# CTL_RELAY_SHEET2_CCU_HAS.net
KiCad netlist of a schematic drawn in Altium Designer
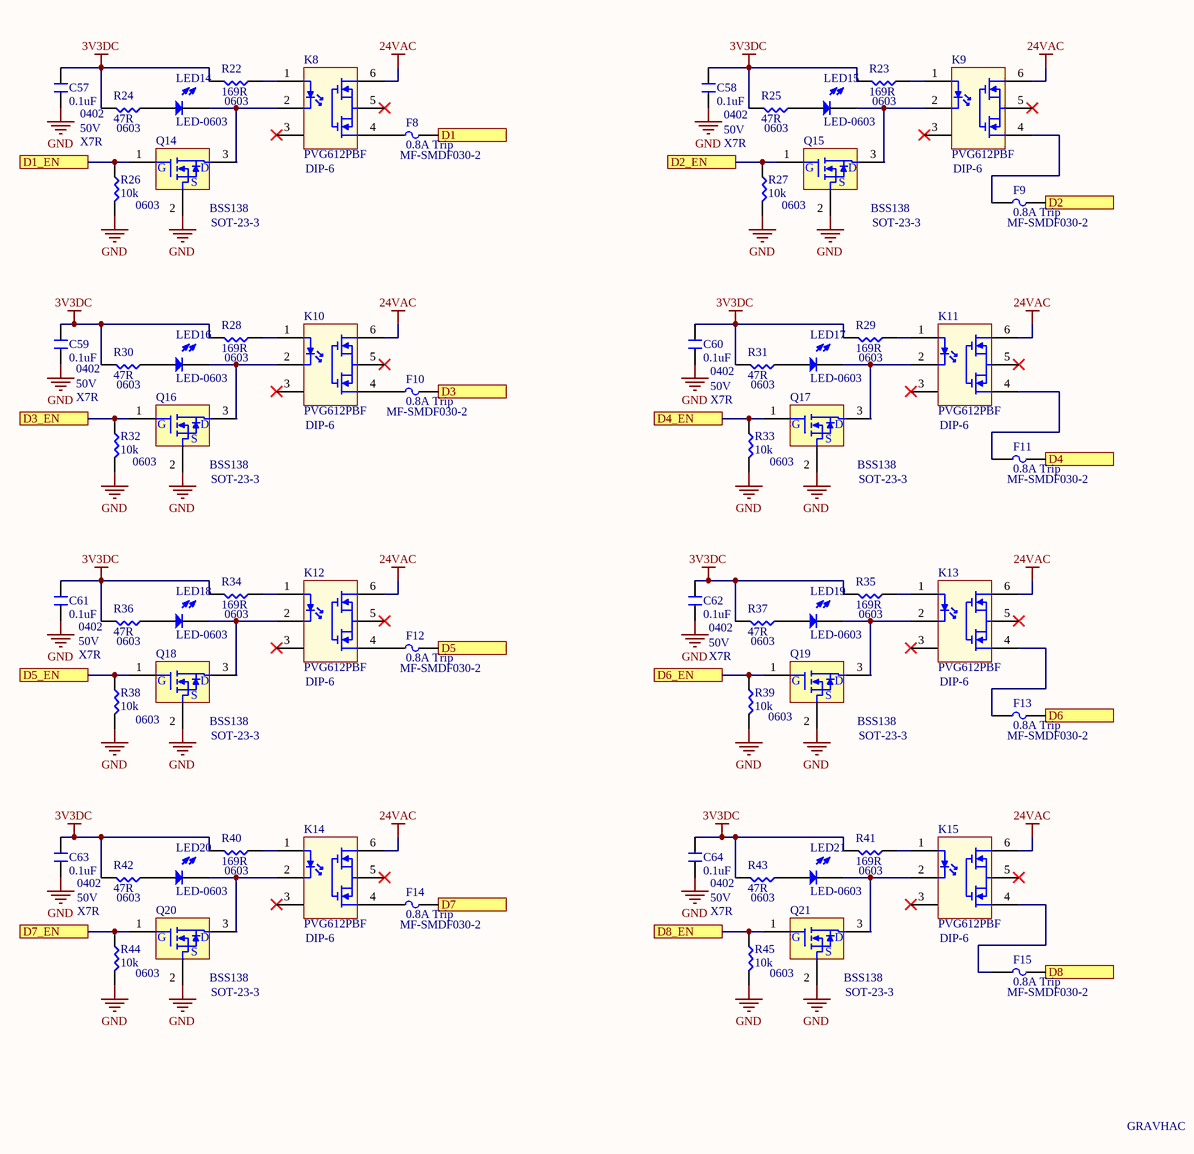
[diagram p0: CTL_RELAY_SHEET2_CCU_HAS.SchDoc]

(export (version "E")
  (design (tool "Eeschema 10.0.6"))
  (components
    (comp (ref "C57")
      (value "0.1uF")
      (footprint "NonPolar-0402")
      (libsource (lib "GravLib") (part "Cap - 0402"))
    )
    (comp (ref "C58")
      (value "0.1uF")
      (footprint "NonPolar-0402")
      (libsource (lib "GravLib") (part "Cap - 0402"))
    )
    (comp (ref "C59")
      (value "0.1uF")
      (footprint "NonPolar-0402")
      (libsource (lib "GravLib") (part "Cap - 0402"))
    )
    (comp (ref "C60")
      (value "0.1uF")
      (footprint "NonPolar-0402")
      (libsource (lib "GravLib") (part "Cap - 0402"))
    )
    (comp (ref "C61")
      (value "0.1uF")
      (footprint "NonPolar-0402")
      (libsource (lib "GravLib") (part "Cap - 0402"))
    )
    (comp (ref "C62")
      (value "0.1uF")
      (footprint "NonPolar-0402")
      (libsource (lib "GravLib") (part "Cap - 0402"))
    )
    (comp (ref "C63")
      (value "0.1uF")
      (footprint "NonPolar-0402")
      (libsource (lib "GravLib") (part "Cap - 0402"))
    )
    (comp (ref "C64")
      (value "0.1uF")
      (footprint "NonPolar-0402")
      (libsource (lib "GravLib") (part "Cap - 0402"))
    )
    (comp (ref "F8")
      (value "0.8A Trip")
      (footprint "Fuse-MF-SMDF030-2")
      (libsource (lib "GravLib") (part "Fuse-MF-SMDF030-2"))
    )
    (comp (ref "F9")
      (value "0.8A Trip")
      (footprint "Fuse-MF-SMDF030-2")
      (libsource (lib "GravLib") (part "Fuse-MF-SMDF030-2"))
    )
    (comp (ref "F10")
      (value "0.8A Trip")
      (footprint "Fuse-MF-SMDF030-2")
      (libsource (lib "GravLib") (part "Fuse-MF-SMDF030-2"))
    )
    (comp (ref "F11")
      (value "0.8A Trip")
      (footprint "Fuse-MF-SMDF030-2")
      (libsource (lib "GravLib") (part "Fuse-MF-SMDF030-2"))
    )
    (comp (ref "F12")
      (value "0.8A Trip")
      (footprint "Fuse-MF-SMDF030-2")
      (libsource (lib "GravLib") (part "Fuse-MF-SMDF030-2"))
    )
    (comp (ref "F13")
      (value "0.8A Trip")
      (footprint "Fuse-MF-SMDF030-2")
      (libsource (lib "GravLib") (part "Fuse-MF-SMDF030-2"))
    )
    (comp (ref "F14")
      (value "0.8A Trip")
      (footprint "Fuse-MF-SMDF030-2")
      (libsource (lib "GravLib") (part "Fuse-MF-SMDF030-2"))
    )
    (comp (ref "F15")
      (value "0.8A Trip")
      (footprint "Fuse-MF-SMDF030-2")
      (libsource (lib "GravLib") (part "Fuse-MF-SMDF030-2"))
    )
    (comp (ref "K8")
      (value "PVG612PBF")
      (footprint "PVG612PBF")
      (description "PhotoVoltaic Relay")
      (libsource (lib "GravLib") (part "PVG612PBF"))
    )
    (comp (ref "K9")
      (value "PVG612PBF")
      (footprint "PVG612PBF")
      (description "PhotoVoltaic Relay")
      (libsource (lib "GravLib") (part "PVG612PBF"))
    )
    (comp (ref "K10")
      (value "PVG612PBF")
      (footprint "PVG612PBF")
      (description "PhotoVoltaic Relay")
      (libsource (lib "GravLib") (part "PVG612PBF"))
    )
    (comp (ref "K11")
      (value "PVG612PBF")
      (footprint "PVG612PBF")
      (description "PhotoVoltaic Relay")
      (libsource (lib "GravLib") (part "PVG612PBF"))
    )
    (comp (ref "K12")
      (value "PVG612PBF")
      (footprint "PVG612PBF")
      (description "PhotoVoltaic Relay")
      (libsource (lib "GravLib") (part "PVG612PBF"))
    )
    (comp (ref "K13")
      (value "PVG612PBF")
      (footprint "PVG612PBF")
      (description "PhotoVoltaic Relay")
      (libsource (lib "GravLib") (part "PVG612PBF"))
    )
    (comp (ref "K14")
      (value "PVG612PBF")
      (footprint "PVG612PBF")
      (description "PhotoVoltaic Relay")
      (libsource (lib "GravLib") (part "PVG612PBF"))
    )
    (comp (ref "K15")
      (value "PVG612PBF")
      (footprint "PVG612PBF")
      (description "PhotoVoltaic Relay")
      (libsource (lib "GravLib") (part "PVG612PBF"))
    )
    (comp (ref "LED14")
      (value "LED-0603")
      (footprint "LED-0603")
      (libsource (lib "GravLib") (part "LED-0603"))
    )
    (comp (ref "LED15")
      (value "LED-0603")
      (footprint "LED-0603")
      (libsource (lib "GravLib") (part "LED-0603"))
    )
    (comp (ref "LED16")
      (value "LED-0603")
      (footprint "LED-0603")
      (libsource (lib "GravLib") (part "LED-0603"))
    )
    (comp (ref "LED17")
      (value "LED-0603")
      (footprint "LED-0603")
      (libsource (lib "GravLib") (part "LED-0603"))
    )
    (comp (ref "LED18")
      (value "LED-0603")
      (footprint "LED-0603")
      (libsource (lib "GravLib") (part "LED-0603"))
    )
    (comp (ref "LED19")
      (value "LED-0603")
      (footprint "LED-0603")
      (libsource (lib "GravLib") (part "LED-0603"))
    )
    (comp (ref "LED20")
      (value "LED-0603")
      (footprint "LED-0603")
      (libsource (lib "GravLib") (part "LED-0603"))
    )
    (comp (ref "LED21")
      (value "LED-0603")
      (footprint "LED-0603")
      (libsource (lib "GravLib") (part "LED-0603"))
    )
    (comp (ref "Q14") (value "BSS138") (footprint "BSS138-SOT23") (libsource (lib "GravLib") (part "BSS138")))
    (comp (ref "Q15") (value "BSS138") (footprint "BSS138-SOT23") (libsource (lib "GravLib") (part "BSS138")))
    (comp (ref "Q16") (value "BSS138") (footprint "BSS138-SOT23") (libsource (lib "GravLib") (part "BSS138")))
    (comp (ref "Q17") (value "BSS138") (footprint "BSS138-SOT23") (libsource (lib "GravLib") (part "BSS138")))
    (comp (ref "Q18") (value "BSS138") (footprint "BSS138-SOT23") (libsource (lib "GravLib") (part "BSS138")))
    (comp (ref "Q19") (value "BSS138") (footprint "BSS138-SOT23") (libsource (lib "GravLib") (part "BSS138")))
    (comp (ref "Q20") (value "BSS138") (footprint "BSS138-SOT23") (libsource (lib "GravLib") (part "BSS138")))
    (comp (ref "Q21") (value "BSS138") (footprint "BSS138-SOT23") (libsource (lib "GravLib") (part "BSS138")))
    (comp (ref "R22")
      (value "169R")
      (footprint "NonPolar-0603")
      (libsource (lib "GravLib") (part "Res - 0603"))
    )
    (comp (ref "R23")
      (value "169R")
      (footprint "NonPolar-0603")
      (libsource (lib "GravLib") (part "Res - 0603"))
    )
    (comp (ref "R24")
      (value "47R")
      (footprint "NonPolar-0603")
      (libsource (lib "GravLib") (part "Res - 0603"))
    )
    (comp (ref "R25")
      (value "47R")
      (footprint "NonPolar-0603")
      (libsource (lib "GravLib") (part "Res - 0603"))
    )
    (comp (ref "R26")
      (value "10k")
      (footprint "NonPolar-0603")
      (libsource (lib "GravLib") (part "Res - 0603"))
    )
    (comp (ref "R27")
      (value "10k")
      (footprint "NonPolar-0603")
      (libsource (lib "GravLib") (part "Res - 0603"))
    )
    (comp (ref "R28")
      (value "169R")
      (footprint "NonPolar-0603")
      (libsource (lib "GravLib") (part "Res - 0603"))
    )
    (comp (ref "R29")
      (value "169R")
      (footprint "NonPolar-0603")
      (libsource (lib "GravLib") (part "Res - 0603"))
    )
    (comp (ref "R30")
      (value "47R")
      (footprint "NonPolar-0603")
      (libsource (lib "GravLib") (part "Res - 0603"))
    )
    (comp (ref "R31")
      (value "47R")
      (footprint "NonPolar-0603")
      (libsource (lib "GravLib") (part "Res - 0603"))
    )
    (comp (ref "R32")
      (value "10k")
      (footprint "NonPolar-0603")
      (libsource (lib "GravLib") (part "Res - 0603"))
    )
    (comp (ref "R33")
      (value "10k")
      (footprint "NonPolar-0603")
      (libsource (lib "GravLib") (part "Res - 0603"))
    )
    (comp (ref "R34")
      (value "169R")
      (footprint "NonPolar-0603")
      (libsource (lib "GravLib") (part "Res - 0603"))
    )
    (comp (ref "R35")
      (value "169R")
      (footprint "NonPolar-0603")
      (libsource (lib "GravLib") (part "Res - 0603"))
    )
    (comp (ref "R36")
      (value "47R")
      (footprint "NonPolar-0603")
      (libsource (lib "GravLib") (part "Res - 0603"))
    )
    (comp (ref "R37")
      (value "47R")
      (footprint "NonPolar-0603")
      (libsource (lib "GravLib") (part "Res - 0603"))
    )
    (comp (ref "R38")
      (value "10k")
      (footprint "NonPolar-0603")
      (libsource (lib "GravLib") (part "Res - 0603"))
    )
    (comp (ref "R39")
      (value "10k")
      (footprint "NonPolar-0603")
      (libsource (lib "GravLib") (part "Res - 0603"))
    )
    (comp (ref "R40")
      (value "169R")
      (footprint "NonPolar-0603")
      (libsource (lib "GravLib") (part "Res - 0603"))
    )
    (comp (ref "R41")
      (value "169R")
      (footprint "NonPolar-0603")
      (libsource (lib "GravLib") (part "Res - 0603"))
    )
    (comp (ref "R42")
      (value "47R")
      (footprint "NonPolar-0603")
      (libsource (lib "GravLib") (part "Res - 0603"))
    )
    (comp (ref "R43")
      (value "47R")
      (footprint "NonPolar-0603")
      (libsource (lib "GravLib") (part "Res - 0603"))
    )
    (comp (ref "R44")
      (value "10k")
      (footprint "NonPolar-0603")
      (libsource (lib "GravLib") (part "Res - 0603"))
    )
    (comp (ref "R45")
      (value "10k")
      (footprint "NonPolar-0603")
      (libsource (lib "GravLib") (part "Res - 0603"))
    )
  )
  (nets
    (net (code "1") (name "/D1") (class "Default")
      (node (ref "F8") (pin "2") (pinfunction "2_2") (pintype "passive"))
    )
    (net (code "2") (name "/D1_EN") (class "Default")
      (node (ref "Q14") (pin "1") (pinfunction "G_1") (pintype "passive"))
      (node (ref "R26") (pin "2") (pinfunction "2_2") (pintype "passive"))
    )
    (net (code "3") (name "/D2") (class "Default")
      (node (ref "F9") (pin "2") (pinfunction "2_2") (pintype "passive"))
    )
    (net (code "4") (name "/D2_EN") (class "Default")
      (node (ref "Q15") (pin "1") (pinfunction "G_1") (pintype "passive"))
      (node (ref "R27") (pin "2") (pinfunction "2_2") (pintype "passive"))
    )
    (net (code "5") (name "/D3") (class "Default")
      (node (ref "F10") (pin "2") (pinfunction "2_2") (pintype "passive"))
    )
    (net (code "6") (name "/D3_EN") (class "Default")
      (node (ref "Q16") (pin "1") (pinfunction "G_1") (pintype "passive"))
      (node (ref "R32") (pin "2") (pinfunction "2_2") (pintype "passive"))
    )
    (net (code "7") (name "/D4") (class "Default")
      (node (ref "F11") (pin "2") (pinfunction "2_2") (pintype "passive"))
    )
    (net (code "8") (name "/D4_EN") (class "Default")
      (node (ref "Q17") (pin "1") (pinfunction "G_1") (pintype "passive"))
      (node (ref "R33") (pin "2") (pinfunction "2_2") (pintype "passive"))
    )
    (net (code "9") (name "/D5") (class "Default")
      (node (ref "F12") (pin "2") (pinfunction "2_2") (pintype "passive"))
    )
    (net (code "10") (name "/D5_EN") (class "Default")
      (node (ref "Q18") (pin "1") (pinfunction "G_1") (pintype "passive"))
      (node (ref "R38") (pin "2") (pinfunction "2_2") (pintype "passive"))
    )
    (net (code "11") (name "/D6") (class "Default")
      (node (ref "F13") (pin "2") (pinfunction "2_2") (pintype "passive"))
    )
    (net (code "12") (name "/D6_EN") (class "Default")
      (node (ref "Q19") (pin "1") (pinfunction "G_1") (pintype "passive"))
      (node (ref "R39") (pin "2") (pinfunction "2_2") (pintype "passive"))
    )
    (net (code "13") (name "/D7") (class "Default")
      (node (ref "F14") (pin "2") (pinfunction "2_2") (pintype "passive"))
    )
    (net (code "14") (name "/D7_EN") (class "Default")
      (node (ref "Q20") (pin "1") (pinfunction "G_1") (pintype "passive"))
      (node (ref "R44") (pin "2") (pinfunction "2_2") (pintype "passive"))
    )
    (net (code "15") (name "/D8") (class "Default")
      (node (ref "F15") (pin "2") (pinfunction "2_2") (pintype "passive"))
    )
    (net (code "16") (name "/D8_EN") (class "Default")
      (node (ref "Q21") (pin "1") (pinfunction "G_1") (pintype "passive"))
      (node (ref "R45") (pin "2") (pinfunction "2_2") (pintype "passive"))
    )
    (net (code "17") (name "3V3DC") (class "Default")
      (node (ref "C57") (pin "2") (pinfunction "2_2") (pintype "passive"))
      (node (ref "C58") (pin "2") (pinfunction "2_2") (pintype "passive"))
      (node (ref "C59") (pin "2") (pinfunction "2_2") (pintype "passive"))
      (node (ref "C60") (pin "2") (pinfunction "2_2") (pintype "passive"))
      (node (ref "C61") (pin "2") (pinfunction "2_2") (pintype "passive"))
      (node (ref "C62") (pin "2") (pinfunction "2_2") (pintype "passive"))
      (node (ref "C63") (pin "2") (pinfunction "2_2") (pintype "passive"))
      (node (ref "C64") (pin "2") (pinfunction "2_2") (pintype "passive"))
      (node (ref "R22") (pin "1") (pinfunction "1_1") (pintype "passive"))
      (node (ref "R23") (pin "1") (pinfunction "1_1") (pintype "passive"))
      (node (ref "R24") (pin "1") (pinfunction "1_1") (pintype "passive"))
      (node (ref "R25") (pin "1") (pinfunction "1_1") (pintype "passive"))
      (node (ref "R28") (pin "1") (pinfunction "1_1") (pintype "passive"))
      (node (ref "R29") (pin "1") (pinfunction "1_1") (pintype "passive"))
      (node (ref "R30") (pin "1") (pinfunction "1_1") (pintype "passive"))
      (node (ref "R31") (pin "1") (pinfunction "1_1") (pintype "passive"))
      (node (ref "R34") (pin "1") (pinfunction "1_1") (pintype "passive"))
      (node (ref "R35") (pin "1") (pinfunction "1_1") (pintype "passive"))
      (node (ref "R36") (pin "1") (pinfunction "1_1") (pintype "passive"))
      (node (ref "R37") (pin "1") (pinfunction "1_1") (pintype "passive"))
      (node (ref "R40") (pin "1") (pinfunction "1_1") (pintype "passive"))
      (node (ref "R41") (pin "1") (pinfunction "1_1") (pintype "passive"))
      (node (ref "R42") (pin "1") (pinfunction "1_1") (pintype "passive"))
      (node (ref "R43") (pin "1") (pinfunction "1_1") (pintype "passive"))
    )
    (net (code "18") (name "24VAC") (class "Default")
      (node (ref "K10") (pin "6") (pinfunction "13_6") (pintype "passive"))
      (node (ref "K11") (pin "6") (pinfunction "13_6") (pintype "passive"))
      (node (ref "K12") (pin "6") (pinfunction "13_6") (pintype "passive"))
      (node (ref "K13") (pin "6") (pinfunction "13_6") (pintype "passive"))
      (node (ref "K14") (pin "6") (pinfunction "13_6") (pintype "passive"))
      (node (ref "K15") (pin "6") (pinfunction "13_6") (pintype "passive"))
      (node (ref "K8") (pin "6") (pinfunction "13_6") (pintype "passive"))
      (node (ref "K9") (pin "6") (pinfunction "13_6") (pintype "passive"))
    )
    (net (code "19") (name "GND") (class "Default")
      (node (ref "C57") (pin "1") (pinfunction "1_1") (pintype "passive"))
      (node (ref "C58") (pin "1") (pinfunction "1_1") (pintype "passive"))
      (node (ref "C59") (pin "1") (pinfunction "1_1") (pintype "passive"))
      (node (ref "C60") (pin "1") (pinfunction "1_1") (pintype "passive"))
      (node (ref "C61") (pin "1") (pinfunction "1_1") (pintype "passive"))
      (node (ref "C62") (pin "1") (pinfunction "1_1") (pintype "passive"))
      (node (ref "C63") (pin "1") (pinfunction "1_1") (pintype "passive"))
      (node (ref "C64") (pin "1") (pinfunction "1_1") (pintype "passive"))
      (node (ref "Q14") (pin "2") (pinfunction "S_2") (pintype "passive"))
      (node (ref "Q15") (pin "2") (pinfunction "S_2") (pintype "passive"))
      (node (ref "Q16") (pin "2") (pinfunction "S_2") (pintype "passive"))
      (node (ref "Q17") (pin "2") (pinfunction "S_2") (pintype "passive"))
      (node (ref "Q18") (pin "2") (pinfunction "S_2") (pintype "passive"))
      (node (ref "Q19") (pin "2") (pinfunction "S_2") (pintype "passive"))
      (node (ref "Q20") (pin "2") (pinfunction "S_2") (pintype "passive"))
      (node (ref "Q21") (pin "2") (pinfunction "S_2") (pintype "passive"))
      (node (ref "R26") (pin "1") (pinfunction "1_1") (pintype "passive"))
      (node (ref "R27") (pin "1") (pinfunction "1_1") (pintype "passive"))
      (node (ref "R32") (pin "1") (pinfunction "1_1") (pintype "passive"))
      (node (ref "R33") (pin "1") (pinfunction "1_1") (pintype "passive"))
      (node (ref "R38") (pin "1") (pinfunction "1_1") (pintype "passive"))
      (node (ref "R39") (pin "1") (pinfunction "1_1") (pintype "passive"))
      (node (ref "R44") (pin "1") (pinfunction "1_1") (pintype "passive"))
      (node (ref "R45") (pin "1") (pinfunction "1_1") (pintype "passive"))
    )
    (net (code "20") (name "Net-(K8-15)") (class "Default")
      (node (ref "F8") (pin "1") (pinfunction "1_1") (pintype "passive"))
      (node (ref "K8") (pin "4") (pinfunction "15_4") (pintype "passive"))
    )
    (net (code "21") (name "Net-(K8-16)") (class "Default")
      (node (ref "K8") (pin "1") (pinfunction "16_1") (pintype "passive"))
      (node (ref "R22") (pin "2") (pinfunction "2_2") (pintype "passive"))
    )
    (net (code "22") (name "Net-(K8-17)") (class "Default")
      (node (ref "K8") (pin "2") (pinfunction "17_2") (pintype "passive"))
      (node (ref "LED14") (pin "2") (pinfunction "2_2") (pintype "passive"))
      (node (ref "Q14") (pin "3") (pinfunction "D_3") (pintype "passive"))
    )
    (net (code "23") (name "Net-(K9-15)") (class "Default")
      (node (ref "F9") (pin "1") (pinfunction "1_1") (pintype "passive"))
      (node (ref "K9") (pin "4") (pinfunction "15_4") (pintype "passive"))
    )
    (net (code "24") (name "Net-(K9-16)") (class "Default")
      (node (ref "K9") (pin "1") (pinfunction "16_1") (pintype "passive"))
      (node (ref "R23") (pin "2") (pinfunction "2_2") (pintype "passive"))
    )
    (net (code "25") (name "Net-(K9-17)") (class "Default")
      (node (ref "K9") (pin "2") (pinfunction "17_2") (pintype "passive"))
      (node (ref "LED15") (pin "2") (pinfunction "2_2") (pintype "passive"))
      (node (ref "Q15") (pin "3") (pinfunction "D_3") (pintype "passive"))
    )
    (net (code "26") (name "Net-(K10-15)") (class "Default")
      (node (ref "F10") (pin "1") (pinfunction "1_1") (pintype "passive"))
      (node (ref "K10") (pin "4") (pinfunction "15_4") (pintype "passive"))
    )
    (net (code "27") (name "Net-(K10-16)") (class "Default")
      (node (ref "K10") (pin "1") (pinfunction "16_1") (pintype "passive"))
      (node (ref "R28") (pin "2") (pinfunction "2_2") (pintype "passive"))
    )
    (net (code "28") (name "Net-(K10-17)") (class "Default")
      (node (ref "K10") (pin "2") (pinfunction "17_2") (pintype "passive"))
      (node (ref "LED16") (pin "2") (pinfunction "2_2") (pintype "passive"))
      (node (ref "Q16") (pin "3") (pinfunction "D_3") (pintype "passive"))
    )
    (net (code "29") (name "Net-(K11-15)") (class "Default")
      (node (ref "F11") (pin "1") (pinfunction "1_1") (pintype "passive"))
      (node (ref "K11") (pin "4") (pinfunction "15_4") (pintype "passive"))
    )
    (net (code "30") (name "Net-(K11-16)") (class "Default")
      (node (ref "K11") (pin "1") (pinfunction "16_1") (pintype "passive"))
      (node (ref "R29") (pin "2") (pinfunction "2_2") (pintype "passive"))
    )
    (net (code "31") (name "Net-(K11-17)") (class "Default")
      (node (ref "K11") (pin "2") (pinfunction "17_2") (pintype "passive"))
      (node (ref "LED17") (pin "2") (pinfunction "2_2") (pintype "passive"))
      (node (ref "Q17") (pin "3") (pinfunction "D_3") (pintype "passive"))
    )
    (net (code "32") (name "Net-(K12-15)") (class "Default")
      (node (ref "F12") (pin "1") (pinfunction "1_1") (pintype "passive"))
      (node (ref "K12") (pin "4") (pinfunction "15_4") (pintype "passive"))
    )
    (net (code "33") (name "Net-(K12-16)") (class "Default")
      (node (ref "K12") (pin "1") (pinfunction "16_1") (pintype "passive"))
      (node (ref "R34") (pin "2") (pinfunction "2_2") (pintype "passive"))
    )
    (net (code "34") (name "Net-(K12-17)") (class "Default")
      (node (ref "K12") (pin "2") (pinfunction "17_2") (pintype "passive"))
      (node (ref "LED18") (pin "2") (pinfunction "2_2") (pintype "passive"))
      (node (ref "Q18") (pin "3") (pinfunction "D_3") (pintype "passive"))
    )
    (net (code "35") (name "Net-(K13-15)") (class "Default")
      (node (ref "F13") (pin "1") (pinfunction "1_1") (pintype "passive"))
      (node (ref "K13") (pin "4") (pinfunction "15_4") (pintype "passive"))
    )
    (net (code "36") (name "Net-(K13-16)") (class "Default")
      (node (ref "K13") (pin "1") (pinfunction "16_1") (pintype "passive"))
      (node (ref "R35") (pin "2") (pinfunction "2_2") (pintype "passive"))
    )
    (net (code "37") (name "Net-(K13-17)") (class "Default")
      (node (ref "K13") (pin "2") (pinfunction "17_2") (pintype "passive"))
      (node (ref "LED19") (pin "2") (pinfunction "2_2") (pintype "passive"))
      (node (ref "Q19") (pin "3") (pinfunction "D_3") (pintype "passive"))
    )
    (net (code "38") (name "Net-(K14-15)") (class "Default")
      (node (ref "F14") (pin "1") (pinfunction "1_1") (pintype "passive"))
      (node (ref "K14") (pin "4") (pinfunction "15_4") (pintype "passive"))
    )
    (net (code "39") (name "Net-(K14-16)") (class "Default")
      (node (ref "K14") (pin "1") (pinfunction "16_1") (pintype "passive"))
      (node (ref "R40") (pin "2") (pinfunction "2_2") (pintype "passive"))
    )
    (net (code "40") (name "Net-(K14-17)") (class "Default")
      (node (ref "K14") (pin "2") (pinfunction "17_2") (pintype "passive"))
      (node (ref "LED20") (pin "2") (pinfunction "2_2") (pintype "passive"))
      (node (ref "Q20") (pin "3") (pinfunction "D_3") (pintype "passive"))
    )
    (net (code "41") (name "Net-(K15-15)") (class "Default")
      (node (ref "F15") (pin "1") (pinfunction "1_1") (pintype "passive"))
      (node (ref "K15") (pin "4") (pinfunction "15_4") (pintype "passive"))
    )
    (net (code "42") (name "Net-(K15-16)") (class "Default")
      (node (ref "K15") (pin "1") (pinfunction "16_1") (pintype "passive"))
      (node (ref "R41") (pin "2") (pinfunction "2_2") (pintype "passive"))
    )
    (net (code "43") (name "Net-(K15-17)") (class "Default")
      (node (ref "K15") (pin "2") (pinfunction "17_2") (pintype "passive"))
      (node (ref "LED21") (pin "2") (pinfunction "2_2") (pintype "passive"))
      (node (ref "Q21") (pin "3") (pinfunction "D_3") (pintype "passive"))
    )
    (net (code "44") (name "Net-(LED14-Pad1)") (class "Default")
      (node (ref "LED14") (pin "1") (pinfunction "1_1") (pintype "passive"))
      (node (ref "R24") (pin "2") (pinfunction "2_2") (pintype "passive"))
    )
    (net (code "45") (name "Net-(LED15-Pad1)") (class "Default")
      (node (ref "LED15") (pin "1") (pinfunction "1_1") (pintype "passive"))
      (node (ref "R25") (pin "2") (pinfunction "2_2") (pintype "passive"))
    )
    (net (code "46") (name "Net-(LED16-Pad1)") (class "Default")
      (node (ref "LED16") (pin "1") (pinfunction "1_1") (pintype "passive"))
      (node (ref "R30") (pin "2") (pinfunction "2_2") (pintype "passive"))
    )
    (net (code "47") (name "Net-(LED17-Pad1)") (class "Default")
      (node (ref "LED17") (pin "1") (pinfunction "1_1") (pintype "passive"))
      (node (ref "R31") (pin "2") (pinfunction "2_2") (pintype "passive"))
    )
    (net (code "48") (name "Net-(LED18-Pad1)") (class "Default")
      (node (ref "LED18") (pin "1") (pinfunction "1_1") (pintype "passive"))
      (node (ref "R36") (pin "2") (pinfunction "2_2") (pintype "passive"))
    )
    (net (code "49") (name "Net-(LED19-Pad1)") (class "Default")
      (node (ref "LED19") (pin "1") (pinfunction "1_1") (pintype "passive"))
      (node (ref "R37") (pin "2") (pinfunction "2_2") (pintype "passive"))
    )
    (net (code "50") (name "Net-(LED20-Pad1)") (class "Default")
      (node (ref "LED20") (pin "1") (pinfunction "1_1") (pintype "passive"))
      (node (ref "R42") (pin "2") (pinfunction "2_2") (pintype "passive"))
    )
    (net (code "51") (name "Net-(LED21-Pad1)") (class "Default")
      (node (ref "LED21") (pin "1") (pinfunction "1_1") (pintype "passive"))
      (node (ref "R43") (pin "2") (pinfunction "2_2") (pintype "passive"))
    )
    (net (code "52") (name "unconnected-(K8-14-Pad5)") (class "Default")
      (node (ref "K8") (pin "5") (pinfunction "14_5") (pintype "passive+no_connect"))
    )
    (net (code "53") (name "unconnected-(K8-18-Pad3)") (class "Default")
      (node (ref "K8") (pin "3") (pinfunction "18_3") (pintype "passive+no_connect"))
    )
    (net (code "54") (name "unconnected-(K9-14-Pad5)") (class "Default")
      (node (ref "K9") (pin "5") (pinfunction "14_5") (pintype "passive+no_connect"))
    )
    (net (code "55") (name "unconnected-(K9-18-Pad3)") (class "Default")
      (node (ref "K9") (pin "3") (pinfunction "18_3") (pintype "passive+no_connect"))
    )
    (net (code "56") (name "unconnected-(K10-14-Pad5)") (class "Default")
      (node (ref "K10") (pin "5") (pinfunction "14_5") (pintype "passive+no_connect"))
    )
    (net (code "57") (name "unconnected-(K10-18-Pad3)") (class "Default")
      (node (ref "K10") (pin "3") (pinfunction "18_3") (pintype "passive+no_connect"))
    )
    (net (code "58") (name "unconnected-(K11-14-Pad5)") (class "Default")
      (node (ref "K11") (pin "5") (pinfunction "14_5") (pintype "passive+no_connect"))
    )
    (net (code "59") (name "unconnected-(K11-18-Pad3)") (class "Default")
      (node (ref "K11") (pin "3") (pinfunction "18_3") (pintype "passive+no_connect"))
    )
    (net (code "60") (name "unconnected-(K12-14-Pad5)") (class "Default")
      (node (ref "K12") (pin "5") (pinfunction "14_5") (pintype "passive+no_connect"))
    )
    (net (code "61") (name "unconnected-(K12-18-Pad3)") (class "Default")
      (node (ref "K12") (pin "3") (pinfunction "18_3") (pintype "passive+no_connect"))
    )
    (net (code "62") (name "unconnected-(K13-14-Pad5)") (class "Default")
      (node (ref "K13") (pin "5") (pinfunction "14_5") (pintype "passive+no_connect"))
    )
    (net (code "63") (name "unconnected-(K13-18-Pad3)") (class "Default")
      (node (ref "K13") (pin "3") (pinfunction "18_3") (pintype "passive+no_connect"))
    )
    (net (code "64") (name "unconnected-(K14-14-Pad5)") (class "Default")
      (node (ref "K14") (pin "5") (pinfunction "14_5") (pintype "passive+no_connect"))
    )
    (net (code "65") (name "unconnected-(K14-18-Pad3)") (class "Default")
      (node (ref "K14") (pin "3") (pinfunction "18_3") (pintype "passive+no_connect"))
    )
    (net (code "66") (name "unconnected-(K15-14-Pad5)") (class "Default")
      (node (ref "K15") (pin "5") (pinfunction "14_5") (pintype "passive+no_connect"))
    )
    (net (code "67") (name "unconnected-(K15-18-Pad3)") (class "Default")
      (node (ref "K15") (pin "3") (pinfunction "18_3") (pintype "passive+no_connect"))
    )
  )
)
